# Flightcontroller.net
KiCad netlist of a schematic drawn in EAGLE
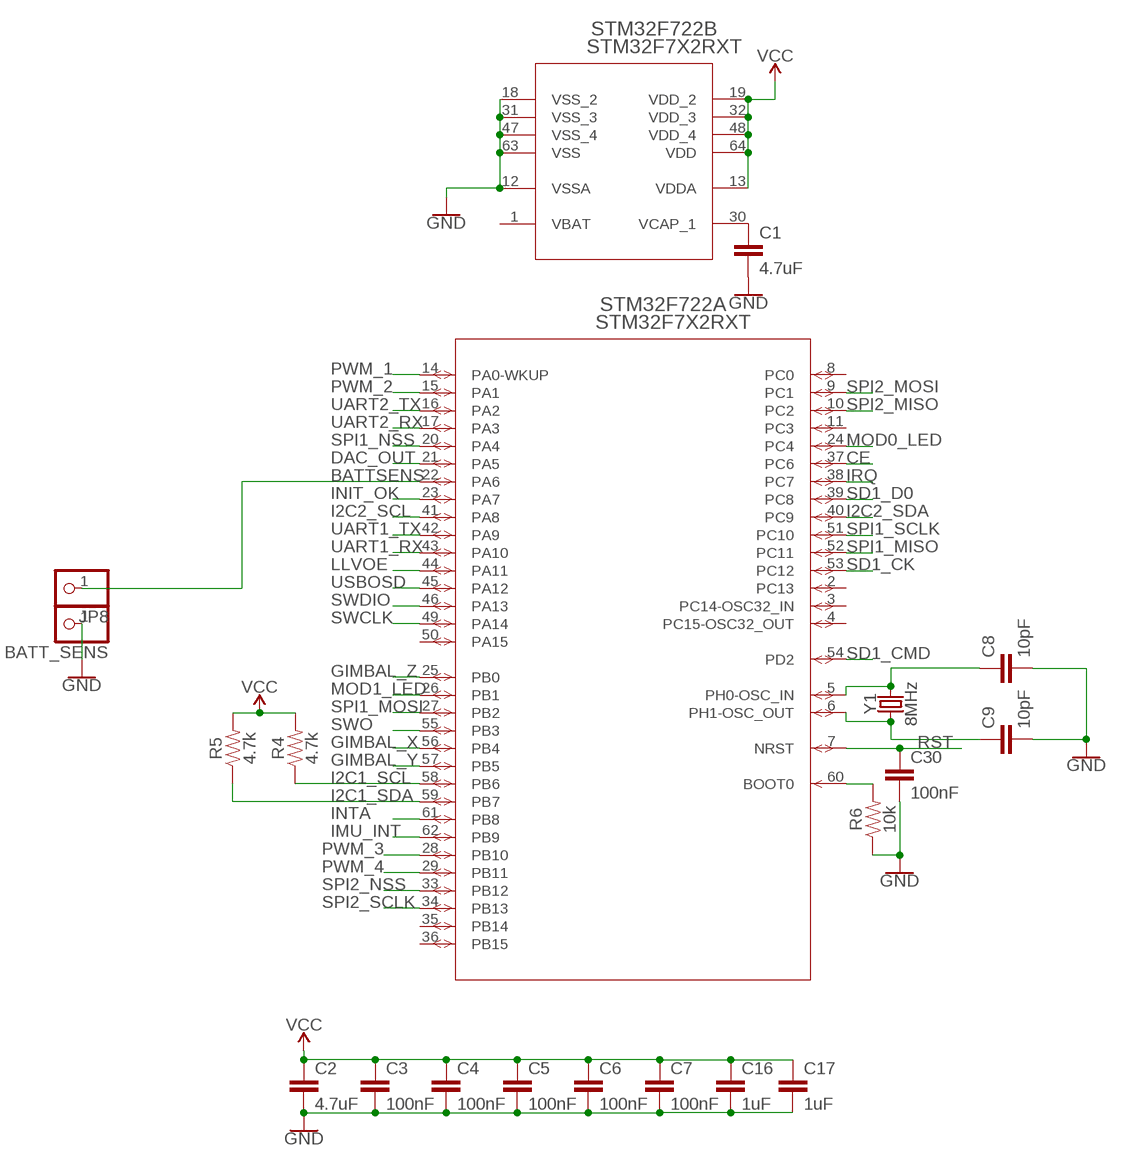
[diagram p0: schematic, sheet 1]
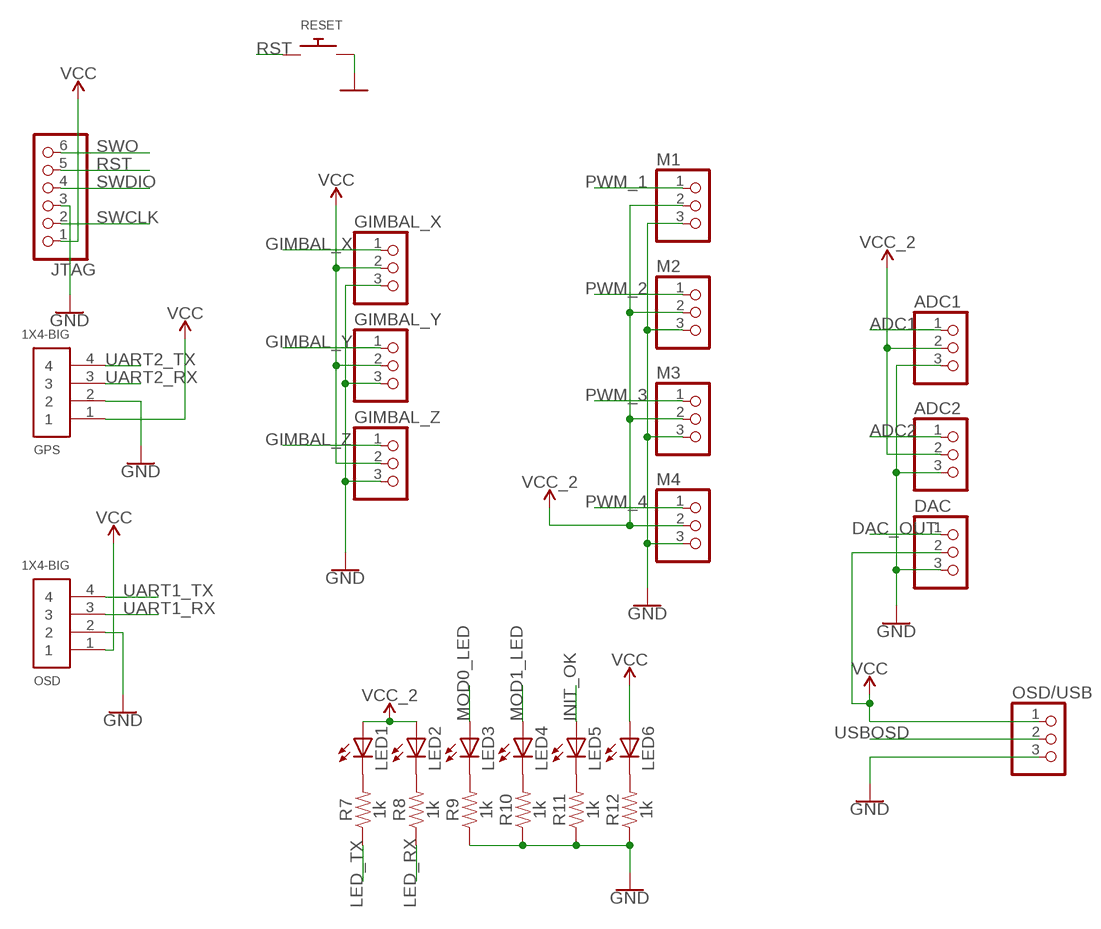
[diagram p1: schematic, sheet 2]
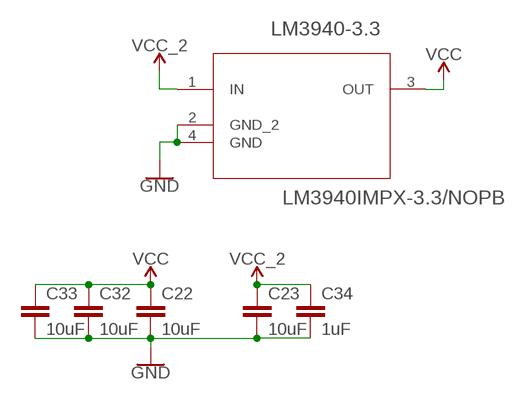
[diagram p2: schematic, sheet 3]
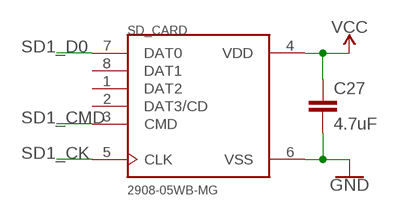
[diagram p3: schematic, sheet 4]
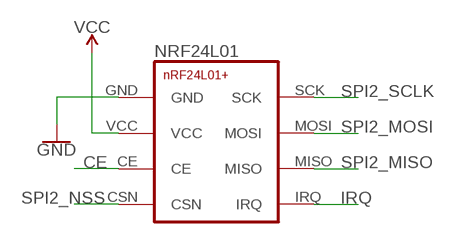
[diagram p4: schematic, sheet 5]
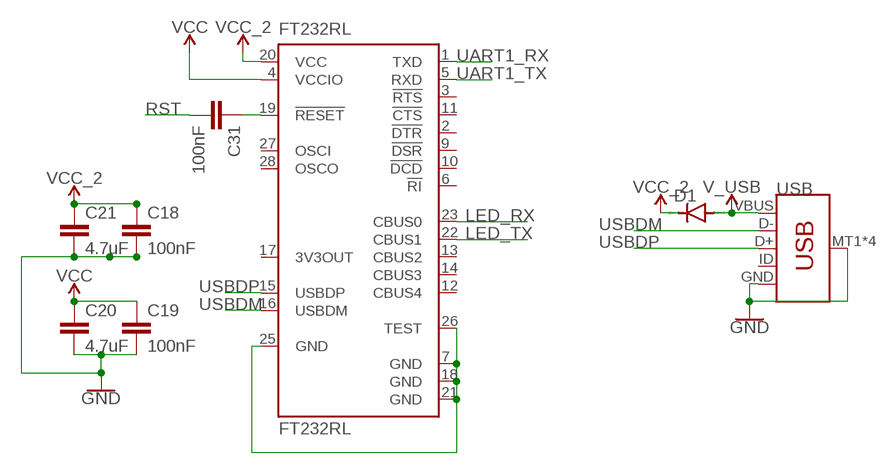
[diagram p5: schematic, sheet 6]
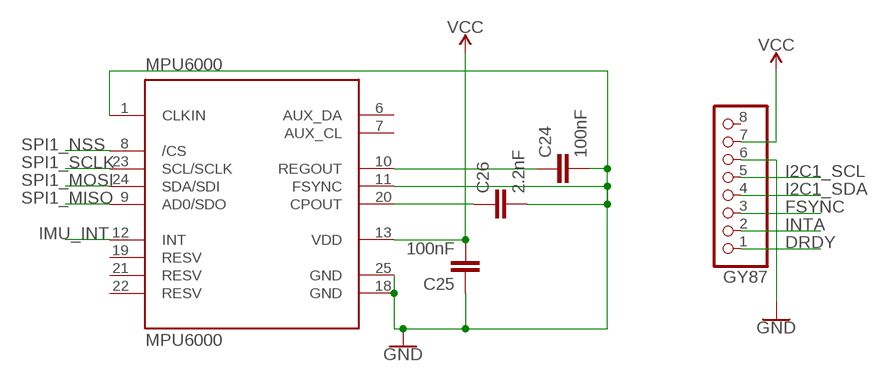
[diagram p6: schematic, sheet 7]
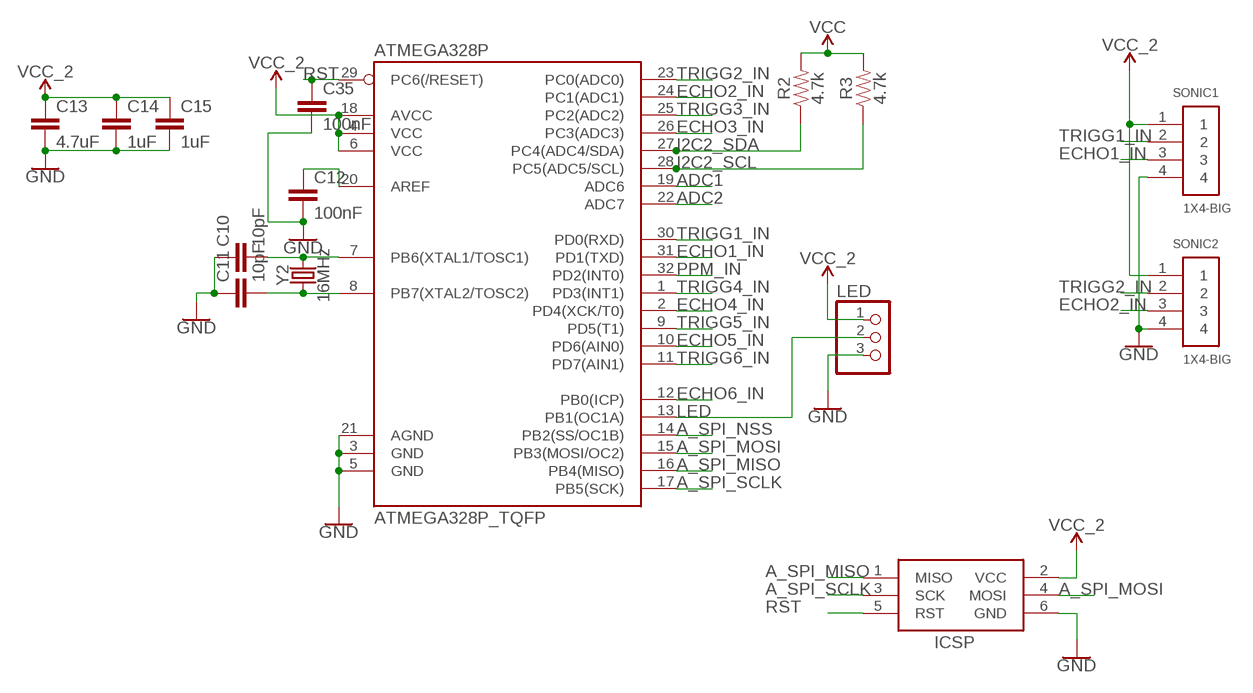
[diagram p7: schematic, sheet 8]
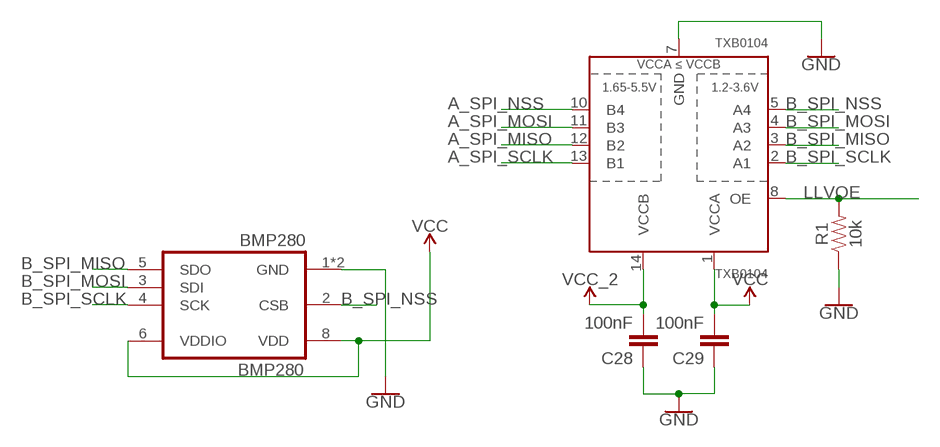
[diagram p8: schematic, sheet 9]
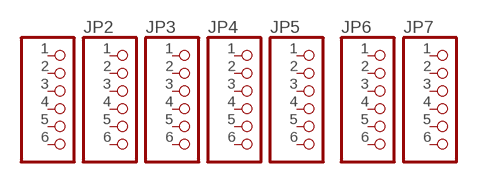
[diagram p9: schematic, sheet 10]

(export (version "E")
  (design (tool "Eeschema 10.0.6"))
  (components
    (comp (ref "C24")
      (value "100nF")
      (footprint "eagle-import:C0805")
      (libsource (lib "eagle-import") (part "C-EUC0805"))
    )
    (comp (ref "C25")
      (value "100nF")
      (footprint "eagle-import:C0805")
      (libsource (lib "eagle-import") (part "C-EUC0805"))
    )
    (comp (ref "C26")
      (value "2.2nF")
      (footprint "eagle-import:C0805")
      (libsource (lib "eagle-import") (part "C-EUC0805"))
    )
    (comp (ref "GY87")
      (value "PINHD-1X8CLEANBIG")
      (footprint "eagle-import:1X08-CLEANBIG")
      (libsource (lib "eagle-import") (part "PINHD-1X8CLEANBIG"))
    )
    (comp (ref "MPU6000")
      (value "MPU6000")
      (footprint "eagle-import:QFN50P400X400X95-25T265X275N")
      (libsource (lib "eagle-import") (part "MPU6000"))
    )
    (comp (ref "C18")
      (value "100nF")
      (footprint "eagle-import:C0805")
      (libsource (lib "eagle-import") (part "C-EUC0805"))
    )
    (comp (ref "C19")
      (value "100nF")
      (footprint "eagle-import:C0805")
      (libsource (lib "eagle-import") (part "C-EUC0805"))
    )
    (comp (ref "C20")
      (value "4.7uF")
      (footprint "eagle-import:C0805")
      (libsource (lib "eagle-import") (part "resistor_348_C-EUC0805"))
    )
    (comp (ref "C21")
      (value "4.7uF")
      (footprint "eagle-import:C0805")
      (libsource (lib "eagle-import") (part "resistor_348_C-EUC0805"))
    )
    (comp (ref "C31")
      (value "100nF")
      (footprint "eagle-import:C0805")
      (libsource (lib "eagle-import") (part "C-EUC0805"))
    )
    (comp (ref "D1")
      (value "DIODE-DO214BA")
      (footprint "eagle-import:DO214BA")
      (libsource (lib "eagle-import") (part "DIODE-DO214BA"))
    )
    (comp (ref "FT232RL")
      (value "FT232RL")
      (footprint "eagle-import:SSOP28")
      (libsource (lib "eagle-import") (part "FT232RL"))
    )
    (comp (ref "USB")
      (value "USB_MICRO-B_SMT")
      (footprint "eagle-import:USB-MICROB")
      (libsource (lib "eagle-import") (part "USB_MICRO-B_SMT"))
    )
    (comp (ref "NRF24L01")
      (value "NRF24L01+")
      (footprint "eagle-import:NRF24L01+")
      (libsource (lib "eagle-import") (part "NRF24L01+"))
    )
    (comp (ref "C22")
      (value "10uF")
      (footprint "eagle-import:C0805")
      (libsource (lib "eagle-import") (part "C-EUC0805"))
    )
    (comp (ref "C23")
      (value "10uF")
      (footprint "eagle-import:C0805")
      (libsource (lib "eagle-import") (part "C-EUC0805"))
    )
    (comp (ref "C32")
      (value "10uF")
      (footprint "eagle-import:C0805")
      (libsource (lib "eagle-import") (part "C-EUC0805"))
    )
    (comp (ref "C33")
      (value "10uF")
      (footprint "eagle-import:C0805")
      (libsource (lib "eagle-import") (part "C-EUC0805"))
    )
    (comp (ref "C34")
      (value "1uF")
      (footprint "eagle-import:C0805")
      (libsource (lib "eagle-import") (part "C-EUC0805"))
    )
    (comp (ref "LM3940-3.3")
      (value "LM3940IMPX-3.3/NOPB")
      (footprint "eagle-import:SOT230P696X180-4N")
      (fields (field (name "MF") "Texas Instruments"))
      (libsource (lib "eagle-import") (part "LM3940IMPX-3.3/NOPB"))
    )
    (comp (ref "C27")
      (value "4.7uF")
      (footprint "eagle-import:C0805")
      (libsource (lib "eagle-import") (part "resistor_348_C-EUC0805"))
    )
    (comp (ref "SD_CARD")
      (value "2908-05WB-MG")
      (footprint "eagle-import:3M_2908-05WB-MG")
      (fields (field (name "MF") "3M"))
      (libsource (lib "eagle-import") (part "2908-05WB-MG"))
    )
    (comp (ref "BMP280")
      (value "BMP280")
      (footprint "eagle-import:BMP280")
      (libsource (lib "eagle-import") (part "BMP280"))
    )
    (comp (ref "C28")
      (value "100nF")
      (footprint "eagle-import:C0805")
      (libsource (lib "eagle-import") (part "C-EUC0805"))
    )
    (comp (ref "C29")
      (value "100nF")
      (footprint "eagle-import:C0805")
      (libsource (lib "eagle-import") (part "C-EUC0805"))
    )
    (comp (ref "R1")
      (value "10k")
      (footprint "eagle-import:0603")
      (libsource (lib "eagle-import") (part "10KOHM-0603-1/10W-1%"))
    )
    (comp (ref "TXB0104")
      (value "TXB0104")
      (footprint "eagle-import:SO14")
      (libsource (lib "eagle-import") (part "TXB0104PWRSOIC14"))
    )
    (comp (ref "ADC1")
      (value "PINHD-1X3")
      (footprint "eagle-import:1X03")
      (libsource (lib "eagle-import") (part "PINHD-1X3"))
    )
    (comp (ref "ADC2")
      (value "PINHD-1X3")
      (footprint "eagle-import:1X03")
      (libsource (lib "eagle-import") (part "PINHD-1X3"))
    )
    (comp (ref "DAC")
      (value "PINHD-1X3")
      (footprint "eagle-import:1X03")
      (libsource (lib "eagle-import") (part "PINHD-1X3"))
    )
    (comp (ref "GIMBAL_X")
      (value "PINHD-1X3")
      (footprint "eagle-import:1X03")
      (libsource (lib "eagle-import") (part "PINHD-1X3"))
    )
    (comp (ref "GIMBAL_Y")
      (value "PINHD-1X3")
      (footprint "eagle-import:1X03")
      (libsource (lib "eagle-import") (part "PINHD-1X3"))
    )
    (comp (ref "GIMBAL_Z")
      (value "PINHD-1X3")
      (footprint "eagle-import:1X03")
      (libsource (lib "eagle-import") (part "PINHD-1X3"))
    )
    (comp (ref "GPS")
      (value "1X4-BIG")
      (footprint "eagle-import:1X04-BIG")
      (libsource (lib "eagle-import") (part "1X4-BIG"))
    )
    (comp (ref "JTAG")
      (value "PINHD-1X6")
      (footprint "eagle-import:1X06")
      (libsource (lib "eagle-import") (part "PINHD-1X6"))
    )
    (comp (ref "LED1")
      (value "LEDSMT1206")
      (footprint "eagle-import:1206")
      (libsource (lib "eagle-import") (part "LEDSMT1206"))
    )
    (comp (ref "LED2")
      (value "LEDSMT1206")
      (footprint "eagle-import:1206")
      (libsource (lib "eagle-import") (part "LEDSMT1206"))
    )
    (comp (ref "LED3")
      (value "LEDSMT1206")
      (footprint "eagle-import:1206")
      (libsource (lib "eagle-import") (part "LEDSMT1206"))
    )
    (comp (ref "LED4")
      (value "LEDSMT1206")
      (footprint "eagle-import:1206")
      (libsource (lib "eagle-import") (part "LEDSMT1206"))
    )
    (comp (ref "LED5")
      (value "LEDSMT1206")
      (footprint "eagle-import:1206")
      (libsource (lib "eagle-import") (part "LEDSMT1206"))
    )
    (comp (ref "LED6")
      (value "LEDSMT1206")
      (footprint "eagle-import:1206")
      (libsource (lib "eagle-import") (part "LEDSMT1206"))
    )
    (comp (ref "M1")
      (value "PINHD-1X3")
      (footprint "eagle-import:1X03")
      (libsource (lib "eagle-import") (part "PINHD-1X3"))
    )
    (comp (ref "M2")
      (value "PINHD-1X3")
      (footprint "eagle-import:1X03")
      (libsource (lib "eagle-import") (part "PINHD-1X3"))
    )
    (comp (ref "M3")
      (value "PINHD-1X3")
      (footprint "eagle-import:1X03")
      (libsource (lib "eagle-import") (part "PINHD-1X3"))
    )
    (comp (ref "M4")
      (value "PINHD-1X3")
      (footprint "eagle-import:1X03")
      (libsource (lib "eagle-import") (part "PINHD-1X3"))
    )
    (comp (ref "OSD")
      (value "1X4-BIG")
      (footprint "eagle-import:1X04-BIG")
      (libsource (lib "eagle-import") (part "1X4-BIG"))
    )
    (comp (ref "OSD/USB")
      (value "PINHD-1X3")
      (footprint "eagle-import:1X03")
      (libsource (lib "eagle-import") (part "PINHD-1X3"))
    )
    (comp (ref "R7")
      (value "1k")
      (footprint "eagle-import:0603")
      (libsource (lib "eagle-import") (part "10KOHM-0603-1/10W-1%"))
    )
    (comp (ref "R8")
      (value "1k")
      (footprint "eagle-import:0603")
      (libsource (lib "eagle-import") (part "10KOHM-0603-1/10W-1%"))
    )
    (comp (ref "R9")
      (value "1k")
      (footprint "eagle-import:0603")
      (libsource (lib "eagle-import") (part "10KOHM-0603-1/10W-1%"))
    )
    (comp (ref "R10")
      (value "1k")
      (footprint "eagle-import:0603")
      (libsource (lib "eagle-import") (part "10KOHM-0603-1/10W-1%"))
    )
    (comp (ref "R11")
      (value "1k")
      (footprint "eagle-import:0603")
      (libsource (lib "eagle-import") (part "10KOHM-0603-1/10W-1%"))
    )
    (comp (ref "R12")
      (value "1k")
      (footprint "eagle-import:0603")
      (libsource (lib "eagle-import") (part "10KOHM-0603-1/10W-1%"))
    )
    (comp (ref "RESET")
      (value "SWITCH_PUSHBUTTONC&K_KSS")
      (footprint "eagle-import:BTN_CK_KSS")
      (libsource (lib "eagle-import") (part "SWITCH_PUSHBUTTONC&K_KSS"))
    )
    (comp (ref "BATT_SENS")
      (value "PINHD-1X1")
      (footprint "eagle-import:1X01")
      (libsource (lib "eagle-import") (part "PINHD-1X1"))
    )
    (comp (ref "C1")
      (value "4.7uF")
      (footprint "eagle-import:C0805")
      (libsource (lib "eagle-import") (part "resistor_348_C-EUC0805"))
    )
    (comp (ref "C2")
      (value "4.7uF")
      (footprint "eagle-import:C0805")
      (libsource (lib "eagle-import") (part "resistor_348_C-EUC0805"))
    )
    (comp (ref "C3")
      (value "100nF")
      (footprint "eagle-import:C0805")
      (libsource (lib "eagle-import") (part "C-EUC0805"))
    )
    (comp (ref "C4")
      (value "100nF")
      (footprint "eagle-import:C0805")
      (libsource (lib "eagle-import") (part "C-EUC0805"))
    )
    (comp (ref "C5")
      (value "100nF")
      (footprint "eagle-import:C0805")
      (libsource (lib "eagle-import") (part "C-EUC0805"))
    )
    (comp (ref "C6")
      (value "100nF")
      (footprint "eagle-import:C0805")
      (libsource (lib "eagle-import") (part "C-EUC0805"))
    )
    (comp (ref "C7")
      (value "100nF")
      (footprint "eagle-import:C0805")
      (libsource (lib "eagle-import") (part "C-EUC0805"))
    )
    (comp (ref "C8")
      (value "10pF")
      (footprint "eagle-import:C0805")
      (libsource (lib "eagle-import") (part "C-EUC0805"))
    )
    (comp (ref "C9")
      (value "10pF")
      (footprint "eagle-import:C0805")
      (libsource (lib "eagle-import") (part "C-EUC0805"))
    )
    (comp (ref "C16")
      (value "1uF")
      (footprint "eagle-import:C0805")
      (libsource (lib "eagle-import") (part "C-EUC0805"))
    )
    (comp (ref "C17")
      (value "1uF")
      (footprint "eagle-import:C0805")
      (libsource (lib "eagle-import") (part "C-EUC0805"))
    )
    (comp (ref "C30")
      (value "100nF")
      (footprint "eagle-import:C0805")
      (libsource (lib "eagle-import") (part "C-EUC0805"))
    )
    (comp (ref "JP8")
      (value "PINHD-1X1")
      (footprint "eagle-import:1X01")
      (libsource (lib "eagle-import") (part "PINHD-1X1"))
    )
    (comp (ref "R4")
      (value "4.7k")
      (footprint "eagle-import:0603")
      (libsource (lib "eagle-import") (part "4.7KOHM-0603-1/10W-1%"))
    )
    (comp (ref "R5")
      (value "4.7k")
      (footprint "eagle-import:0603")
      (libsource (lib "eagle-import") (part "4.7KOHM-0603-1/10W-1%"))
    )
    (comp (ref "R6")
      (value "10k")
      (footprint "eagle-import:0603")
      (libsource (lib "eagle-import") (part "10KOHM-0603-1/10W-1%"))
    )
    (comp (ref "STM32F722")
      (value "STM32F7X2RXT")
      (footprint "eagle-import:LQFP64-10X10MM")
      (libsource (lib "eagle-import") (part "STM32F7X2RXT"))
    )
    (comp (ref "Y1")
      (value "8MHz")
      (footprint "eagle-import:CRYSTAL-SMD-5X3.2-4PAD")
      (libsource (lib "eagle-import") (part "CRYSTAL-8MHZSMD-5X3.2"))
    )
    (comp (ref "ATMEGA328P")
      (value "ATMEGA328P_TQFP")
      (footprint "eagle-import:TQFP32-08")
      (libsource (lib "eagle-import") (part "ATMEGA328P_TQFP"))
    )
    (comp (ref "C10")
      (value "10pF")
      (footprint "eagle-import:C0805")
      (libsource (lib "eagle-import") (part "C-EUC0805"))
    )
    (comp (ref "C11")
      (value "10pF")
      (footprint "eagle-import:C0805")
      (libsource (lib "eagle-import") (part "C-EUC0805"))
    )
    (comp (ref "C12")
      (value "100nF")
      (footprint "eagle-import:C0805")
      (libsource (lib "eagle-import") (part "C-EUC0805"))
    )
    (comp (ref "C13")
      (value "4.7uF")
      (footprint "eagle-import:C0805")
      (libsource (lib "eagle-import") (part "resistor_348_C-EUC0805"))
    )
    (comp (ref "C14")
      (value "1uF")
      (footprint "eagle-import:C0805")
      (libsource (lib "eagle-import") (part "C-EUC0805"))
    )
    (comp (ref "C15")
      (value "1uF")
      (footprint "eagle-import:C0805")
      (libsource (lib "eagle-import") (part "C-EUC0805"))
    )
    (comp (ref "C35")
      (value "100nF")
      (footprint "eagle-import:C0805")
      (libsource (lib "eagle-import") (part "C-EUC0805"))
    )
    (comp (ref "ICSP")
      (value "AVRISP-6")
      (footprint "eagle-import:AVRISP")
      (libsource (lib "eagle-import") (part "AVRISP-6"))
    )
    (comp (ref "LED")
      (value "PINHD-1X3")
      (footprint "eagle-import:1X03")
      (libsource (lib "eagle-import") (part "PINHD-1X3"))
    )
    (comp (ref "R2")
      (value "4.7k")
      (footprint "eagle-import:0603")
      (libsource (lib "eagle-import") (part "4.7KOHM-0603-1/10W-1%"))
    )
    (comp (ref "R3")
      (value "4.7k")
      (footprint "eagle-import:0603")
      (libsource (lib "eagle-import") (part "4.7KOHM-0603-1/10W-1%"))
    )
    (comp (ref "SONIC1")
      (value "1X4-BIG")
      (footprint "eagle-import:1X04-BIG")
      (libsource (lib "eagle-import") (part "1X4-BIG"))
    )
    (comp (ref "SONIC2")
      (value "1X4-BIG")
      (footprint "eagle-import:1X04-BIG")
      (libsource (lib "eagle-import") (part "1X4-BIG"))
    )
    (comp (ref "Y2")
      (value "16MHz")
      (footprint "eagle-import:CRYSTAL-SMD-5X3.2-4PAD")
      (libsource (lib "eagle-import") (part "CRYSTAL-16MHZSMD-5X3.2"))
    )
    (comp (ref "JP1")
      (value "PINHD-1X6")
      (footprint "eagle-import:1X06")
      (libsource (lib "eagle-import") (part "PINHD-1X6"))
    )
    (comp (ref "JP2")
      (value "PINHD-1X6")
      (footprint "eagle-import:1X06")
      (libsource (lib "eagle-import") (part "PINHD-1X6"))
    )
    (comp (ref "JP3")
      (value "PINHD-1X6")
      (footprint "eagle-import:1X06")
      (libsource (lib "eagle-import") (part "PINHD-1X6"))
    )
    (comp (ref "JP4")
      (value "PINHD-1X6")
      (footprint "eagle-import:1X06")
      (libsource (lib "eagle-import") (part "PINHD-1X6"))
    )
    (comp (ref "JP5")
      (value "PINHD-1X6")
      (footprint "eagle-import:1X06")
      (libsource (lib "eagle-import") (part "PINHD-1X6"))
    )
    (comp (ref "JP6")
      (value "PINHD-1X6")
      (footprint "eagle-import:1X06")
      (libsource (lib "eagle-import") (part "PINHD-1X6"))
    )
    (comp (ref "JP7")
      (value "PINHD-1X6")
      (footprint "eagle-import:1X06")
      (libsource (lib "eagle-import") (part "PINHD-1X6"))
    )
  )
  (nets
    (net (code "1") (name "ADC1") (class "Default")
      (node (ref "ADC1") (pin "1") (pinfunction "1_1") (pintype "passive"))
      (node (ref "ATMEGA328P") (pin "19") (pinfunction "ADC6_19") (pintype "bidirectional"))
    )
    (net (code "2") (name "ADC2") (class "Default")
      (node (ref "ADC2") (pin "1") (pinfunction "1_1") (pintype "passive"))
      (node (ref "ATMEGA328P") (pin "22") (pinfunction "ADC7_22") (pintype "bidirectional"))
    )
    (net (code "3") (name "A_SPI_MISO") (class "Default")
      (node (ref "ATMEGA328P") (pin "16") (pinfunction "PB4(MISO)_16") (pintype "bidirectional"))
      (node (ref "ICSP") (pin "1") (pinfunction "MISO_1") (pintype "input"))
      (node (ref "TXB0104") (pin "12") (pinfunction "B2_12") (pintype "bidirectional"))
    )
    (net (code "4") (name "A_SPI_MOSI") (class "Default")
      (node (ref "ATMEGA328P") (pin "15") (pinfunction "PB3(MOSI/OC2)_15") (pintype "bidirectional"))
      (node (ref "ICSP") (pin "4") (pinfunction "MOSI_4") (pintype "output"))
      (node (ref "TXB0104") (pin "11") (pinfunction "B3_11") (pintype "bidirectional"))
    )
    (net (code "5") (name "A_SPI_NSS") (class "Default")
      (node (ref "ATMEGA328P") (pin "14") (pinfunction "PB2(SS/OC1B)_14") (pintype "bidirectional"))
      (node (ref "TXB0104") (pin "10") (pinfunction "B4_10") (pintype "bidirectional"))
    )
    (net (code "6") (name "A_SPI_SCLK") (class "Default")
      (node (ref "ATMEGA328P") (pin "17") (pinfunction "PB5(SCK)_17") (pintype "bidirectional"))
      (node (ref "ICSP") (pin "3") (pinfunction "SCK_3") (pintype "output"))
      (node (ref "TXB0104") (pin "13") (pinfunction "B1_13") (pintype "bidirectional"))
    )
    (net (code "7") (name "BATTSENS") (class "Default")
      (node (ref "JP8") (pin "1") (pinfunction "1_1") (pintype "passive"))
      (node (ref "STM32F722") (pin "22") (pinfunction "PA6_22") (pintype "bidirectional"))
    )
    (net (code "8") (name "B_SPI_MISO") (class "Default")
      (node (ref "BMP280") (pin "5") (pinfunction "SDO_5") (pintype "input"))
      (node (ref "TXB0104") (pin "3") (pinfunction "A2_3") (pintype "bidirectional"))
    )
    (net (code "9") (name "B_SPI_MOSI") (class "Default")
      (node (ref "BMP280") (pin "3") (pinfunction "SDI_3") (pintype "bidirectional"))
      (node (ref "TXB0104") (pin "4") (pinfunction "A3_4") (pintype "bidirectional"))
    )
    (net (code "10") (name "B_SPI_NSS") (class "Default")
      (node (ref "BMP280") (pin "2") (pinfunction "CSB_2") (pintype "input"))
      (node (ref "TXB0104") (pin "5") (pinfunction "A4_5") (pintype "bidirectional"))
    )
    (net (code "11") (name "B_SPI_SCLK") (class "Default")
      (node (ref "BMP280") (pin "4") (pinfunction "SCK_4") (pintype "bidirectional"))
      (node (ref "TXB0104") (pin "2") (pinfunction "A1_2") (pintype "bidirectional"))
    )
    (net (code "12") (name "CE") (class "Default")
      (node (ref "NRF24L01") (pin "CE") (pinfunction "CE_CE") (pintype "bidirectional"))
      (node (ref "STM32F722") (pin "37") (pinfunction "PC6_37") (pintype "bidirectional"))
    )
    (net (code "13") (name "DAC_OUT") (class "Default")
      (node (ref "DAC") (pin "1") (pinfunction "1_1") (pintype "passive"))
      (node (ref "STM32F722") (pin "21") (pinfunction "PA5_21") (pintype "bidirectional"))
    )
    (net (code "14") (name "DRDY") (class "Default")
      (node (ref "GY87") (pin "1") (pinfunction "1_1") (pintype "passive"))
    )
    (net (code "15") (name "ECHO1_IN") (class "Default")
      (node (ref "ATMEGA328P") (pin "31") (pinfunction "PD1(TXD)_31") (pintype "bidirectional"))
      (node (ref "SONIC1") (pin "3") (pinfunction "3_3") (pintype "bidirectional"))
    )
    (net (code "16") (name "ECHO2_IN") (class "Default")
      (node (ref "ATMEGA328P") (pin "24") (pinfunction "PC1(ADC1)_24") (pintype "bidirectional"))
      (node (ref "SONIC2") (pin "3") (pinfunction "3_3") (pintype "bidirectional"))
    )
    (net (code "17") (name "ECHO3_IN") (class "Default")
      (node (ref "ATMEGA328P") (pin "26") (pinfunction "PC3(ADC3)_26") (pintype "bidirectional"))
    )
    (net (code "18") (name "ECHO4_IN") (class "Default")
      (node (ref "ATMEGA328P") (pin "2") (pinfunction "PD4(XCK/T0)_2") (pintype "bidirectional"))
    )
    (net (code "19") (name "ECHO5_IN") (class "Default")
      (node (ref "ATMEGA328P") (pin "10") (pinfunction "PD6(AIN0)_10") (pintype "bidirectional"))
    )
    (net (code "20") (name "ECHO6_IN") (class "Default")
      (node (ref "ATMEGA328P") (pin "12") (pinfunction "PB0(ICP)_12") (pintype "bidirectional"))
    )
    (net (code "21") (name "FSYNC") (class "Default")
      (node (ref "GY87") (pin "3") (pinfunction "3_3") (pintype "passive"))
    )
    (net (code "22") (name "GIMBAL_X") (class "Default")
      (node (ref "GIMBAL_X") (pin "1") (pinfunction "1_1") (pintype "passive"))
      (node (ref "STM32F722") (pin "56") (pinfunction "PB4_56") (pintype "bidirectional"))
    )
    (net (code "23") (name "GIMBAL_Y") (class "Default")
      (node (ref "GIMBAL_Y") (pin "1") (pinfunction "1_1") (pintype "passive"))
      (node (ref "STM32F722") (pin "57") (pinfunction "PB5_57") (pintype "bidirectional"))
    )
    (net (code "24") (name "GIMBAL_Z") (class "Default")
      (node (ref "GIMBAL_Z") (pin "1") (pinfunction "1_1") (pintype "passive"))
      (node (ref "STM32F722") (pin "25") (pinfunction "PB0_25") (pintype "bidirectional"))
    )
    (net (code "25") (name "GND") (class "Default")
      (node (ref "ADC1") (pin "3") (pinfunction "3_3") (pintype "passive"))
      (node (ref "ADC2") (pin "3") (pinfunction "3_3") (pintype "passive"))
      (node (ref "ATMEGA328P") (pin "21") (pinfunction "AGND_21") (pintype "bidirectional"))
      (node (ref "ATMEGA328P") (pin "3") (pinfunction "GND_3") (pintype "bidirectional"))
      (node (ref "ATMEGA328P") (pin "5") (pinfunction "GND_5") (pintype "bidirectional"))
      (node (ref "BATT_SENS") (pin "1") (pinfunction "1_1") (pintype "passive"))
      (node (ref "BMP280") (pin "1") (pinfunction "GND_1") (pintype "power_in"))
      (node (ref "BMP280") (pin "7") (pinfunction "GND_7") (pintype "power_in"))
      (node (ref "C1") (pin "2") (pinfunction "2_2") (pintype "passive"))
      (node (ref "C10") (pin "1") (pinfunction "1_1") (pintype "passive"))
      (node (ref "C11") (pin "1") (pinfunction "1_1") (pintype "passive"))
      (node (ref "C12") (pin "2") (pinfunction "2_2") (pintype "passive"))
      (node (ref "C13") (pin "2") (pinfunction "2_2") (pintype "passive"))
      (node (ref "C14") (pin "2") (pinfunction "2_2") (pintype "passive"))
      (node (ref "C15") (pin "2") (pinfunction "2_2") (pintype "passive"))
      (node (ref "C16") (pin "2") (pinfunction "2_2") (pintype "passive"))
      (node (ref "C17") (pin "2") (pinfunction "2_2") (pintype "passive"))
      (node (ref "C18") (pin "2") (pinfunction "2_2") (pintype "passive"))
      (node (ref "C19") (pin "2") (pinfunction "2_2") (pintype "passive"))
      (node (ref "C2") (pin "2") (pinfunction "2_2") (pintype "passive"))
      (node (ref "C20") (pin "2") (pinfunction "2_2") (pintype "passive"))
      (node (ref "C21") (pin "2") (pinfunction "2_2") (pintype "passive"))
      (node (ref "C22") (pin "2") (pinfunction "2_2") (pintype "passive"))
      (node (ref "C23") (pin "2") (pinfunction "2_2") (pintype "passive"))
      (node (ref "C24") (pin "2") (pinfunction "2_2") (pintype "passive"))
      (node (ref "C25") (pin "1") (pinfunction "1_1") (pintype "passive"))
      (node (ref "C26") (pin "2") (pinfunction "2_2") (pintype "passive"))
      (node (ref "C27") (pin "2") (pinfunction "2_2") (pintype "passive"))
      (node (ref "C28") (pin "1") (pinfunction "1_1") (pintype "passive"))
      (node (ref "C29") (pin "1") (pinfunction "1_1") (pintype "passive"))
      (node (ref "C3") (pin "2") (pinfunction "2_2") (pintype "passive"))
      (node (ref "C30") (pin "2") (pinfunction "2_2") (pintype "passive"))
      (node (ref "C32") (pin "2") (pinfunction "2_2") (pintype "passive"))
      (node (ref "C33") (pin "2") (pinfunction "2_2") (pintype "passive"))
      (node (ref "C34") (pin "2") (pinfunction "2_2") (pintype "passive"))
      (node (ref "C35") (pin "2") (pinfunction "2_2") (pintype "passive"))
      (node (ref "C4") (pin "2") (pinfunction "2_2") (pintype "passive"))
      (node (ref "C5") (pin "2") (pinfunction "2_2") (pintype "passive"))
      (node (ref "C6") (pin "2") (pinfunction "2_2") (pintype "passive"))
      (node (ref "C7") (pin "2") (pinfunction "2_2") (pintype "passive"))
      (node (ref "C8") (pin "2") (pinfunction "2_2") (pintype "passive"))
      (node (ref "C9") (pin "2") (pinfunction "2_2") (pintype "passive"))
      (node (ref "DAC") (pin "3") (pinfunction "3_3") (pintype "passive"))
      (node (ref "GIMBAL_X") (pin "3") (pinfunction "3_3") (pintype "passive"))
      (node (ref "GIMBAL_Y") (pin "3") (pinfunction "3_3") (pintype "passive"))
      (node (ref "GIMBAL_Z") (pin "3") (pinfunction "3_3") (pintype "passive"))
      (node (ref "GPS") (pin "2") (pinfunction "2_2") (pintype "bidirectional"))
      (node (ref "GY87") (pin "6") (pinfunction "6_6") (pintype "passive"))
      (node (ref "ICSP") (pin "6") (pinfunction "GND_6") (pintype "power_in"))
      (node (ref "JTAG") (pin "3") (pinfunction "3_3") (pintype "passive"))
      (node (ref "LED") (pin "3") (pinfunction "3_3") (pintype "passive"))
      (node (ref "LM3940-3.3") (pin "2") (pinfunction "GND_2_2") (pintype "passive"))
      (node (ref "LM3940-3.3") (pin "4") (pinfunction "GND_4") (pintype "passive"))
      (node (ref "M1") (pin "3") (pinfunction "3_3") (pintype "passive"))
      (node (ref "M2") (pin "3") (pinfunction "3_3") (pintype "passive"))
      (node (ref "M3") (pin "3") (pinfunction "3_3") (pintype "passive"))
      (node (ref "M4") (pin "3") (pinfunction "3_3") (pintype "passive"))
      (node (ref "MPU6000") (pin "1") (pinfunction "CLKIN_1") (pintype "input"))
      (node (ref "MPU6000") (pin "11") (pinfunction "FSYNC_11") (pintype "input"))
      (node (ref "MPU6000") (pin "18") (pinfunction "GND_18") (pintype "power_in"))
      (node (ref "MPU6000") (pin "25") (pinfunction "GND_25") (pintype "power_in"))
      (node (ref "NRF24L01") (pin "GND") (pinfunction "GND_GND") (pintype "power_in"))
      (node (ref "OSD") (pin "2") (pinfunction "2_2") (pintype "bidirectional"))
      (node (ref "OSD/USB") (pin "3") (pinfunction "3_3") (pintype "passive"))
      (node (ref "R1") (pin "1") (pinfunction "1_1") (pintype "passive"))
      (node (ref "R10") (pin "1") (pinfunction "1_1") (pintype "passive"))
      (node (ref "R11") (pin "1") (pinfunction "1_1") (pintype "passive"))
      (node (ref "R12") (pin "1") (pinfunction "1_1") (pintype "passive"))
      (node (ref "R6") (pin "1") (pinfunction "1_1") (pintype "passive"))
      (node (ref "R9") (pin "1") (pinfunction "1_1") (pintype "passive"))
      (node (ref "RESET") (pin "P$2") (pinfunction "P$2_P$2") (pintype "passive"))
      (node (ref "SD_CARD") (pin "6") (pinfunction "VSS_6") (pintype "power_in"))
      (node (ref "SONIC1") (pin "4") (pinfunction "4_4") (pintype "bidirectional"))
      (node (ref "SONIC2") (pin "4") (pinfunction "4_4") (pintype "bidirectional"))
      (node (ref "STM32F722") (pin "12") (pinfunction "VSSA_12") (pintype "power_in"))
      (node (ref "STM32F722") (pin "18") (pinfunction "VSS_2_18") (pintype "power_in"))
      (node (ref "STM32F722") (pin "31") (pinfunction "VSS_3_31") (pintype "power_in"))
      (node (ref "STM32F722") (pin "47") (pinfunction "VSS_4_47") (pintype "power_in"))
      (node (ref "STM32F722") (pin "63") (pinfunction "VSS_63") (pintype "power_in"))
      (node (ref "TXB0104") (pin "7") (pinfunction "GND_7") (pintype "bidirectional"))
      (node (ref "USB") (pin "GND") (pinfunction "GND_GND") (pintype "power_in"))
      (node (ref "USB") (pin "MT1") (pinfunction "SHIELD_MT1") (pintype "bidirectional"))
      (node (ref "USB") (pin "MT2") (pinfunction "SHIELD_MT2") (pintype "bidirectional"))
      (node (ref "USB") (pin "P$1") (pinfunction "SHIELD_P$1") (pintype "bidirectional"))
      (node (ref "USB") (pin "P$2") (pinfunction "SHIELD_P$2") (pintype "bidirectional"))
    )
    (net (code "26") (name "I2C1_SCL") (class "Default")
      (node (ref "GY87") (pin "5") (pinfunction "5_5") (pintype "passive"))
      (node (ref "R4") (pin "1") (pinfunction "1_1") (pintype "passive"))
      (node (ref "STM32F722") (pin "58") (pinfunction "PB6_58") (pintype "bidirectional"))
    )
    (net (code "27") (name "I2C1_SDA") (class "Default")
      (node (ref "GY87") (pin "4") (pinfunction "4_4") (pintype "passive"))
      (node (ref "R5") (pin "1") (pinfunction "1_1") (pintype "passive"))
      (node (ref "STM32F722") (pin "59") (pinfunction "PB7_59") (pintype "bidirectional"))
    )
    (net (code "28") (name "I2C2_SCL") (class "Default")
      (node (ref "ATMEGA328P") (pin "28") (pinfunction "PC5(ADC5/SCL)_28") (pintype "bidirectional"))
      (node (ref "R3") (pin "1") (pinfunction "1_1") (pintype "passive"))
      (node (ref "STM32F722") (pin "41") (pinfunction "PA8_41") (pintype "bidirectional"))
    )
    (net (code "29") (name "I2C2_SDA") (class "Default")
      (node (ref "ATMEGA328P") (pin "27") (pinfunction "PC4(ADC4/SDA)_27") (pintype "bidirectional"))
      (node (ref "R2") (pin "1") (pinfunction "1_1") (pintype "passive"))
      (node (ref "STM32F722") (pin "40") (pinfunction "PC9_40") (pintype "bidirectional"))
    )
    (net (code "30") (name "IMU_INT") (class "Default")
      (node (ref "MPU6000") (pin "12") (pinfunction "INT_12") (pintype "open_collector"))
      (node (ref "STM32F722") (pin "62") (pinfunction "PB9_62") (pintype "bidirectional"))
    )
    (net (code "31") (name "INIT_OK") (class "Default")
      (node (ref "LED5") (pin "A") (pinfunction "A_A") (pintype "passive"))
      (node (ref "STM32F722") (pin "23") (pinfunction "PA7_23") (pintype "bidirectional"))
    )
    (net (code "32") (name "INTA") (class "Default")
      (node (ref "GY87") (pin "2") (pinfunction "2_2") (pintype "passive"))
      (node (ref "STM32F722") (pin "61") (pinfunction "PB8_61") (pintype "bidirectional"))
    )
    (net (code "33") (name "IRQ") (class "Default")
      (node (ref "NRF24L01") (pin "IRQ") (pinfunction "IRQ_IRQ") (pintype "bidirectional"))
      (node (ref "STM32F722") (pin "38") (pinfunction "PC7_38") (pintype "bidirectional"))
    )
    (net (code "34") (name "LED") (class "Default")
      (node (ref "ATMEGA328P") (pin "13") (pinfunction "PB1(OC1A)_13") (pintype "bidirectional"))
      (node (ref "LED") (pin "2") (pinfunction "2_2") (pintype "passive"))
    )
    (net (code "35") (name "LED_RX") (class "Default")
      (node (ref "FT232RL") (pin "23") (pinfunction "CBUS0_23") (pintype "bidirectional"))
      (node (ref "R8") (pin "1") (pinfunction "1_1") (pintype "passive"))
    )
    (net (code "36") (name "LED_TX") (class "Default")
      (node (ref "FT232RL") (pin "22") (pinfunction "CBUS1_22") (pintype "bidirectional"))
      (node (ref "R7") (pin "1") (pinfunction "1_1") (pintype "passive"))
    )
    (net (code "37") (name "LLVOE") (class "Default")
      (node (ref "R1") (pin "2") (pinfunction "2_2") (pintype "passive"))
      (node (ref "STM32F722") (pin "44") (pinfunction "PA11_44") (pintype "bidirectional"))
      (node (ref "TXB0104") (pin "8") (pinfunction "OE_8") (pintype "bidirectional"))
    )
    (net (code "38") (name "MOD0_LED") (class "Default")
      (node (ref "LED3") (pin "A") (pinfunction "A_A") (pintype "passive"))
      (node (ref "STM32F722") (pin "24") (pinfunction "PC4_24") (pintype "bidirectional"))
    )
    (net (code "39") (name "MOD1_LED") (class "Default")
      (node (ref "LED4") (pin "A") (pinfunction "A_A") (pintype "passive"))
      (node (ref "STM32F722") (pin "26") (pinfunction "PB1_26") (pintype "bidirectional"))
    )
    (net (code "40") (name "Net-(ATMEGA328P-AREF)") (class "Default")
      (node (ref "ATMEGA328P") (pin "20") (pinfunction "AREF_20") (pintype "bidirectional"))
      (node (ref "C12") (pin "1") (pinfunction "1_1") (pintype "passive"))
    )
    (net (code "41") (name "Net-(ATMEGA328P-PB6(XTAL1{slash}TOSC1))") (class "Default")
      (node (ref "ATMEGA328P") (pin "7") (pinfunction "PB6(XTAL1/TOSC1)_7") (pintype "bidirectional"))
      (node (ref "C10") (pin "2") (pinfunction "2_2") (pintype "passive"))
      (node (ref "Y2") (pin "3") (pinfunction "2_3") (pintype "passive"))
    )
    (net (code "42") (name "Net-(ATMEGA328P-PB7(XTAL2{slash}TOSC2))") (class "Default")
      (node (ref "ATMEGA328P") (pin "8") (pinfunction "PB7(XTAL2/TOSC2)_8") (pintype "bidirectional"))
      (node (ref "C11") (pin "2") (pinfunction "2_2") (pintype "passive"))
      (node (ref "Y2") (pin "1") (pinfunction "1_1") (pintype "passive"))
    )
    (net (code "43") (name "Net-(FT232RL-TEST)") (class "Default")
      (node (ref "FT232RL") (pin "18") (pinfunction "GND_18") (pintype "power_in"))
      (node (ref "FT232RL") (pin "21") (pinfunction "GND_21") (pintype "power_in"))
      (node (ref "FT232RL") (pin "25") (pinfunction "GND_25") (pintype "power_in"))
      (node (ref "FT232RL") (pin "26") (pinfunction "TEST_26") (pintype "input"))
      (node (ref "FT232RL") (pin "7") (pinfunction "GND_7") (pintype "power_in"))
    )
    (net (code "44") (name "Net-(FT232RL-~{RESET})") (class "Default")
      (node (ref "C31") (pin "1") (pinfunction "1_1") (pintype "passive"))
      (node (ref "FT232RL") (pin "19") (pinfunction "~{RESET}_19") (pintype "input"))
    )
    (net (code "45") (name "Net-(LED1-PadC)") (class "Default")
      (node (ref "LED1") (pin "C") (pinfunction "C_C") (pintype "passive"))
      (node (ref "R7") (pin "2") (pinfunction "2_2") (pintype "passive"))
    )
    (net (code "46") (name "Net-(LED2-PadC)") (class "Default")
      (node (ref "LED2") (pin "C") (pinfunction "C_C") (pintype "passive"))
      (node (ref "R8") (pin "2") (pinfunction "2_2") (pintype "passive"))
    )
    (net (code "47") (name "Net-(LED3-PadC)") (class "Default")
      (node (ref "LED3") (pin "C") (pinfunction "C_C") (pintype "passive"))
      (node (ref "R9") (pin "2") (pinfunction "2_2") (pintype "passive"))
    )
    (net (code "48") (name "Net-(LED4-PadC)") (class "Default")
      (node (ref "LED4") (pin "C") (pinfunction "C_C") (pintype "passive"))
      (node (ref "R10") (pin "2") (pinfunction "2_2") (pintype "passive"))
    )
    (net (code "49") (name "Net-(LED5-PadC)") (class "Default")
      (node (ref "LED5") (pin "C") (pinfunction "C_C") (pintype "passive"))
      (node (ref "R11") (pin "2") (pinfunction "2_2") (pintype "passive"))
    )
    (net (code "50") (name "Net-(LED6-PadC)") (class "Default")
      (node (ref "LED6") (pin "C") (pinfunction "C_C") (pintype "passive"))
      (node (ref "R12") (pin "2") (pinfunction "2_2") (pintype "passive"))
    )
    (net (code "51") (name "Net-(MPU6000A-CPOUT)") (class "Default")
      (node (ref "C26") (pin "1") (pinfunction "1_1") (pintype "passive"))
      (node (ref "MPU6000") (pin "20") (pinfunction "CPOUT_20") (pintype "output"))
    )
    (net (code "52") (name "Net-(MPU6000A-REGOUT)") (class "Default")
      (node (ref "C24") (pin "1") (pinfunction "1_1") (pintype "passive"))
      (node (ref "MPU6000") (pin "10") (pinfunction "REGOUT_10") (pintype "output"))
    )
    (net (code "53") (name "Net-(STM32F722A-BOOT0)") (class "Default")
      (node (ref "R6") (pin "2") (pinfunction "2_2") (pintype "passive"))
      (node (ref "STM32F722") (pin "60") (pinfunction "BOOT0_60") (pintype "input"))
    )
    (net (code "54") (name "Net-(STM32F722A-PH0-OSC_IN)") (class "Default")
      (node (ref "C8") (pin "1") (pinfunction "1_1") (pintype "passive"))
      (node (ref "STM32F722") (pin "5") (pinfunction "PH0-OSC_IN_5") (pintype "bidirectional"))
      (node (ref "Y1") (pin "3") (pinfunction "2_3") (pintype "passive"))
    )
    (net (code "55") (name "Net-(STM32F722A-PH1-OSC_OUT)") (class "Default")
      (node (ref "C9") (pin "1") (pinfunction "1_1") (pintype "passive"))
      (node (ref "STM32F722") (pin "6") (pinfunction "PH1-OSC_OUT_6") (pintype "bidirectional"))
      (node (ref "Y1") (pin "1") (pinfunction "1_1") (pintype "passive"))
    )
    (net (code "56") (name "Net-(STM32F722B-VCAP_1)") (class "Default")
      (node (ref "C1") (pin "1") (pinfunction "1_1") (pintype "passive"))
      (node (ref "STM32F722") (pin "30") (pinfunction "VCAP_1_30") (pintype "power_in"))
    )
    (net (code "57") (name "PPM_IN") (class "Default")
      (node (ref "ATMEGA328P") (pin "32") (pinfunction "PD2(INT0)_32") (pintype "bidirectional"))
    )
    (net (code "58") (name "PWM_1") (class "Default")
      (node (ref "M1") (pin "1") (pinfunction "1_1") (pintype "passive"))
      (node (ref "STM32F722") (pin "14") (pinfunction "PA0-WKUP_14") (pintype "bidirectional"))
    )
    (net (code "59") (name "PWM_2") (class "Default")
      (node (ref "M2") (pin "1") (pinfunction "1_1") (pintype "passive"))
      (node (ref "STM32F722") (pin "15") (pinfunction "PA1_15") (pintype "bidirectional"))
    )
    (net (code "60") (name "PWM_3") (class "Default")
      (node (ref "M3") (pin "1") (pinfunction "1_1") (pintype "passive"))
      (node (ref "STM32F722") (pin "28") (pinfunction "PB10_28") (pintype "bidirectional"))
    )
    (net (code "61") (name "PWM_4") (class "Default")
      (node (ref "M4") (pin "1") (pinfunction "1_1") (pintype "passive"))
      (node (ref "STM32F722") (pin "29") (pinfunction "PB11_29") (pintype "bidirectional"))
    )
    (net (code "62") (name "RST") (class "Default")
      (node (ref "ATMEGA328P") (pin "29") (pinfunction "PC6(/RESET)_29") (pintype "bidirectional"))
      (node (ref "C30") (pin "1") (pinfunction "1_1") (pintype "passive"))
      (node (ref "C31") (pin "2") (pinfunction "2_2") (pintype "passive"))
      (node (ref "C35") (pin "1") (pinfunction "1_1") (pintype "passive"))
      (node (ref "ICSP") (pin "5") (pinfunction "RST_5") (pintype "output"))
      (node (ref "JTAG") (pin "5") (pinfunction "5_5") (pintype "passive"))
      (node (ref "RESET") (pin "P$1") (pinfunction "P$1_P$1") (pintype "passive"))
      (node (ref "STM32F722") (pin "7") (pinfunction "NRST_7") (pintype "bidirectional"))
    )
    (net (code "63") (name "SD1_CK") (class "Default")
      (node (ref "SD_CARD") (pin "5") (pinfunction "CLK_5") (pintype "bidirectional"))
      (node (ref "STM32F722") (pin "53") (pinfunction "PC12_53") (pintype "bidirectional"))
    )
    (net (code "64") (name "SD1_CMD") (class "Default")
      (node (ref "SD_CARD") (pin "3") (pinfunction "CMD_3") (pintype "bidirectional"))
      (node (ref "STM32F722") (pin "54") (pinfunction "PD2_54") (pintype "bidirectional"))
    )
    (net (code "65") (name "SD1_D0") (class "Default")
      (node (ref "SD_CARD") (pin "7") (pinfunction "DAT0_7") (pintype "bidirectional"))
      (node (ref "STM32F722") (pin "39") (pinfunction "PC8_39") (pintype "bidirectional"))
    )
    (net (code "66") (name "SPI1_MISO") (class "Default")
      (node (ref "MPU6000") (pin "9") (pinfunction "AD0/SDO_9") (pintype "bidirectional"))
      (node (ref "STM32F722") (pin "52") (pinfunction "PC11_52") (pintype "bidirectional"))
    )
    (net (code "67") (name "SPI1_MOSI") (class "Default")
      (node (ref "MPU6000") (pin "24") (pinfunction "SDA/SDI_24") (pintype "bidirectional"))
      (node (ref "STM32F722") (pin "27") (pinfunction "PB2_27") (pintype "bidirectional"))
    )
    (net (code "68") (name "SPI1_NSS") (class "Default")
      (node (ref "MPU6000") (pin "8") (pinfunction "/CS_8") (pintype "input"))
      (node (ref "STM32F722") (pin "20") (pinfunction "PA4_20") (pintype "bidirectional"))
    )
    (net (code "69") (name "SPI1_SCLK") (class "Default")
      (node (ref "MPU6000") (pin "23") (pinfunction "SCL/SCLK_23") (pintype "input"))
      (node (ref "STM32F722") (pin "51") (pinfunction "PC10_51") (pintype "bidirectional"))
    )
    (net (code "70") (name "SPI2_MISO") (class "Default")
      (node (ref "NRF24L01") (pin "MISO") (pinfunction "MISO_MISO") (pintype "bidirectional"))
      (node (ref "STM32F722") (pin "10") (pinfunction "PC2_10") (pintype "bidirectional"))
    )
    (net (code "71") (name "SPI2_MOSI") (class "Default")
      (node (ref "NRF24L01") (pin "MOSI") (pinfunction "MOSI_MOSI") (pintype "bidirectional"))
      (node (ref "STM32F722") (pin "9") (pinfunction "PC1_9") (pintype "bidirectional"))
    )
    (net (code "72") (name "SPI2_NSS") (class "Default")
      (node (ref "NRF24L01") (pin "CSN") (pinfunction "CSN_CSN") (pintype "bidirectional"))
      (node (ref "STM32F722") (pin "33") (pinfunction "PB12_33") (pintype "bidirectional"))
    )
    (net (code "73") (name "SPI2_SCLK") (class "Default")
      (node (ref "NRF24L01") (pin "SCK") (pinfunction "SCK_SCK") (pintype "bidirectional"))
      (node (ref "STM32F722") (pin "34") (pinfunction "PB13_34") (pintype "bidirectional"))
    )
    (net (code "74") (name "SWCLK") (class "Default")
      (node (ref "JTAG") (pin "2") (pinfunction "2_2") (pintype "passive"))
      (node (ref "STM32F722") (pin "49") (pinfunction "PA14_49") (pintype "bidirectional"))
    )
    (net (code "75") (name "SWDIO") (class "Default")
      (node (ref "JTAG") (pin "4") (pinfunction "4_4") (pintype "passive"))
      (node (ref "STM32F722") (pin "46") (pinfunction "PA13_46") (pintype "bidirectional"))
    )
    (net (code "76") (name "SWO") (class "Default")
      (node (ref "JTAG") (pin "6") (pinfunction "6_6") (pintype "passive"))
      (node (ref "STM32F722") (pin "55") (pinfunction "PB3_55") (pintype "bidirectional"))
    )
    (net (code "77") (name "TRIGG1_IN") (class "Default")
      (node (ref "ATMEGA328P") (pin "30") (pinfunction "PD0(RXD)_30") (pintype "bidirectional"))
      (node (ref "SONIC1") (pin "2") (pinfunction "2_2") (pintype "bidirectional"))
    )
    (net (code "78") (name "TRIGG2_IN") (class "Default")
      (node (ref "ATMEGA328P") (pin "23") (pinfunction "PC0(ADC0)_23") (pintype "bidirectional"))
      (node (ref "SONIC2") (pin "2") (pinfunction "2_2") (pintype "bidirectional"))
    )
    (net (code "79") (name "TRIGG3_IN") (class "Default")
      (node (ref "ATMEGA328P") (pin "25") (pinfunction "PC2(ADC2)_25") (pintype "bidirectional"))
    )
    (net (code "80") (name "TRIGG4_IN") (class "Default")
      (node (ref "ATMEGA328P") (pin "1") (pinfunction "PD3(INT1)_1") (pintype "bidirectional"))
    )
    (net (code "81") (name "TRIGG5_IN") (class "Default")
      (node (ref "ATMEGA328P") (pin "9") (pinfunction "PD5(T1)_9") (pintype "bidirectional"))
    )
    (net (code "82") (name "TRIGG6_IN") (class "Default")
      (node (ref "ATMEGA328P") (pin "11") (pinfunction "PD7(AIN1)_11") (pintype "bidirectional"))
    )
    (net (code "83") (name "UART1_RX") (class "Default")
      (node (ref "FT232RL") (pin "1") (pinfunction "TXD_1") (pintype "output"))
      (node (ref "OSD") (pin "3") (pinfunction "3_3") (pintype "bidirectional"))
      (node (ref "STM32F722") (pin "43") (pinfunction "PA10_43") (pintype "bidirectional"))
    )
    (net (code "84") (name "UART1_TX") (class "Default")
      (node (ref "FT232RL") (pin "5") (pinfunction "RXD_5") (pintype "input"))
      (node (ref "OSD") (pin "4") (pinfunction "4_4") (pintype "bidirectional"))
      (node (ref "STM32F722") (pin "42") (pinfunction "PA9_42") (pintype "bidirectional"))
    )
    (net (code "85") (name "UART2_RX") (class "Default")
      (node (ref "GPS") (pin "3") (pinfunction "3_3") (pintype "bidirectional"))
      (node (ref "STM32F722") (pin "17") (pinfunction "PA3_17") (pintype "bidirectional"))
    )
    (net (code "86") (name "UART2_TX") (class "Default")
      (node (ref "GPS") (pin "4") (pinfunction "4_4") (pintype "bidirectional"))
      (node (ref "STM32F722") (pin "16") (pinfunction "PA2_16") (pintype "bidirectional"))
    )
    (net (code "87") (name "USBDM") (class "Default")
      (node (ref "FT232RL") (pin "16") (pinfunction "USBDM_16") (pintype "bidirectional"))
      (node (ref "USB") (pin "D-") (pinfunction "D-_D-") (pintype "bidirectional"))
    )
    (net (code "88") (name "USBDP") (class "Default")
      (node (ref "FT232RL") (pin "15") (pinfunction "USBDP_15") (pintype "bidirectional"))
      (node (ref "USB") (pin "D+") (pinfunction "D+_D+") (pintype "bidirectional"))
    )
    (net (code "89") (name "USBOSD") (class "Default")
      (node (ref "OSD/USB") (pin "2") (pinfunction "2_2") (pintype "passive"))
      (node (ref "STM32F722") (pin "45") (pinfunction "PA12_45") (pintype "bidirectional"))
    )
    (net (code "90") (name "VBAT") (class "Default")
      (node (ref "STM32F722") (pin "1") (pinfunction "VBAT_1") (pintype "power_in"))
    )
    (net (code "91") (name "VCC") (class "Default")
      (node (ref "BMP280") (pin "6") (pinfunction "VDDIO_6") (pintype "power_in"))
      (node (ref "BMP280") (pin "8") (pinfunction "VDD_8") (pintype "power_in"))
      (node (ref "C16") (pin "1") (pinfunction "1_1") (pintype "passive"))
      (node (ref "C17") (pin "1") (pinfunction "1_1") (pintype "passive"))
      (node (ref "C19") (pin "1") (pinfunction "1_1") (pintype "passive"))
      (node (ref "C2") (pin "1") (pinfunction "1_1") (pintype "passive"))
      (node (ref "C20") (pin "1") (pinfunction "1_1") (pintype "passive"))
      (node (ref "C22") (pin "1") (pinfunction "1_1") (pintype "passive"))
      (node (ref "C25") (pin "2") (pinfunction "2_2") (pintype "passive"))
      (node (ref "C27") (pin "1") (pinfunction "1_1") (pintype "passive"))
      (node (ref "C29") (pin "2") (pinfunction "2_2") (pintype "passive"))
      (node (ref "C3") (pin "1") (pinfunction "1_1") (pintype "passive"))
      (node (ref "C32") (pin "1") (pinfunction "1_1") (pintype "passive"))
      (node (ref "C33") (pin "1") (pinfunction "1_1") (pintype "passive"))
      (node (ref "C4") (pin "1") (pinfunction "1_1") (pintype "passive"))
      (node (ref "C5") (pin "1") (pinfunction "1_1") (pintype "passive"))
      (node (ref "C6") (pin "1") (pinfunction "1_1") (pintype "passive"))
      (node (ref "C7") (pin "1") (pinfunction "1_1") (pintype "passive"))
      (node (ref "DAC") (pin "2") (pinfunction "2_2") (pintype "passive"))
      (node (ref "FT232RL") (pin "4") (pinfunction "VCCIO_4") (pintype "power_in"))
      (node (ref "GIMBAL_X") (pin "2") (pinfunction "2_2") (pintype "passive"))
      (node (ref "GIMBAL_Y") (pin "2") (pinfunction "2_2") (pintype "passive"))
      (node (ref "GIMBAL_Z") (pin "2") (pinfunction "2_2") (pintype "passive"))
      (node (ref "GPS") (pin "1") (pinfunction "1_1") (pintype "bidirectional"))
      (node (ref "GY87") (pin "7") (pinfunction "7_7") (pintype "passive"))
      (node (ref "JTAG") (pin "1") (pinfunction "1_1") (pintype "passive"))
      (node (ref "LED6") (pin "A") (pinfunction "A_A") (pintype "passive"))
      (node (ref "LM3940-3.3") (pin "3") (pinfunction "OUT_3") (pintype "output"))
      (node (ref "MPU6000") (pin "13") (pinfunction "VDD_13") (pintype "power_in"))
      (node (ref "NRF24L01") (pin "VCC") (pinfunction "VCC_VCC") (pintype "power_in"))
      (node (ref "OSD") (pin "1") (pinfunction "1_1") (pintype "bidirectional"))
      (node (ref "OSD/USB") (pin "1") (pinfunction "1_1") (pintype "passive"))
      (node (ref "R2") (pin "2") (pinfunction "2_2") (pintype "passive"))
      (node (ref "R3") (pin "2") (pinfunction "2_2") (pintype "passive"))
      (node (ref "R4") (pin "2") (pinfunction "2_2") (pintype "passive"))
      (node (ref "R5") (pin "2") (pinfunction "2_2") (pintype "passive"))
      (node (ref "SD_CARD") (pin "4") (pinfunction "VDD_4") (pintype "power_in"))
      (node (ref "STM32F722") (pin "13") (pinfunction "VDDA_13") (pintype "power_in"))
      (node (ref "STM32F722") (pin "19") (pinfunction "VDD_2_19") (pintype "power_in"))
      (node (ref "STM32F722") (pin "32") (pinfunction "VDD_3_32") (pintype "power_in"))
      (node (ref "STM32F722") (pin "48") (pinfunction "VDD_4_48") (pintype "power_in"))
      (node (ref "STM32F722") (pin "64") (pinfunction "VDD_64") (pintype "power_in"))
      (node (ref "TXB0104") (pin "1") (pinfunction "VCCA_1") (pintype "bidirectional"))
    )
    (net (code "92") (name "VCC_2") (class "Default")
      (node (ref "ADC1") (pin "2") (pinfunction "2_2") (pintype "passive"))
      (node (ref "ADC2") (pin "2") (pinfunction "2_2") (pintype "passive"))
      (node (ref "ATMEGA328P") (pin "18") (pinfunction "AVCC_18") (pintype "bidirectional"))
      (node (ref "ATMEGA328P") (pin "4") (pinfunction "VCC_4") (pintype "bidirectional"))
      (node (ref "ATMEGA328P") (pin "6") (pinfunction "VCC_6") (pintype "bidirectional"))
      (node (ref "C13") (pin "1") (pinfunction "1_1") (pintype "passive"))
      (node (ref "C14") (pin "1") (pinfunction "1_1") (pintype "passive"))
      (node (ref "C15") (pin "1") (pinfunction "1_1") (pintype "passive"))
      (node (ref "C18") (pin "1") (pinfunction "1_1") (pintype "passive"))
      (node (ref "C21") (pin "1") (pinfunction "1_1") (pintype "passive"))
      (node (ref "C23") (pin "1") (pinfunction "1_1") (pintype "passive"))
      (node (ref "C28") (pin "2") (pinfunction "2_2") (pintype "passive"))
      (node (ref "C34") (pin "1") (pinfunction "1_1") (pintype "passive"))
      (node (ref "D1") (pin "C") (pinfunction "C_C") (pintype "passive"))
      (node (ref "FT232RL") (pin "20") (pinfunction "VCC_20") (pintype "power_in"))
      (node (ref "ICSP") (pin "2") (pinfunction "VCC_2") (pintype "power_in"))
      (node (ref "LED") (pin "1") (pinfunction "1_1") (pintype "passive"))
      (node (ref "LED1") (pin "A") (pinfunction "A_A") (pintype "passive"))
      (node (ref "LED2") (pin "A") (pinfunction "A_A") (pintype "passive"))
      (node (ref "LM3940-3.3") (pin "1") (pinfunction "IN_1") (pintype "power_in"))
      (node (ref "M1") (pin "2") (pinfunction "2_2") (pintype "passive"))
      (node (ref "M2") (pin "2") (pinfunction "2_2") (pintype "passive"))
      (node (ref "M3") (pin "2") (pinfunction "2_2") (pintype "passive"))
      (node (ref "M4") (pin "2") (pinfunction "2_2") (pintype "passive"))
      (node (ref "SONIC1") (pin "1") (pinfunction "1_1") (pintype "bidirectional"))
      (node (ref "SONIC2") (pin "1") (pinfunction "1_1") (pintype "bidirectional"))
      (node (ref "TXB0104") (pin "14") (pinfunction "VCCB_14") (pintype "bidirectional"))
    )
    (net (code "93") (name "V_USB") (class "Default")
      (node (ref "D1") (pin "A") (pinfunction "A_A") (pintype "passive"))
      (node (ref "USB") (pin "VBUS") (pinfunction "VBUS_VBUS") (pintype "power_in"))
    )
    (net (code "94") (name "unconnected-(FT232RL-3V3OUT-Pad17)") (class "Default")
      (node (ref "FT232RL") (pin "17") (pinfunction "3V3OUT_17") (pintype "output"))
    )
    (net (code "95") (name "unconnected-(FT232RL-CBUS2-Pad13)") (class "Default")
      (node (ref "FT232RL") (pin "13") (pinfunction "CBUS2_13") (pintype "bidirectional"))
    )
    (net (code "96") (name "unconnected-(FT232RL-CBUS3-Pad14)") (class "Default")
      (node (ref "FT232RL") (pin "14") (pinfunction "CBUS3_14") (pintype "bidirectional"))
    )
    (net (code "97") (name "unconnected-(FT232RL-CBUS4-Pad12)") (class "Default")
      (node (ref "FT232RL") (pin "12") (pinfunction "CBUS4_12") (pintype "bidirectional"))
    )
    (net (code "98") (name "unconnected-(FT232RL-OSCI-Pad27)") (class "Default")
      (node (ref "FT232RL") (pin "27") (pinfunction "OSCI_27") (pintype "input"))
    )
    (net (code "99") (name "unconnected-(FT232RL-OSCO-Pad28)") (class "Default")
      (node (ref "FT232RL") (pin "28") (pinfunction "OSCO_28") (pintype "output"))
    )
    (net (code "100") (name "unconnected-(FT232RL-~{CTS}-Pad11)") (class "Default")
      (node (ref "FT232RL") (pin "11") (pinfunction "~{CTS}_11") (pintype "input"))
    )
    (net (code "101") (name "unconnected-(FT232RL-~{DCD}-Pad10)") (class "Default")
      (node (ref "FT232RL") (pin "10") (pinfunction "~{DCD}_10") (pintype "input"))
    )
    (net (code "102") (name "unconnected-(FT232RL-~{DSR}-Pad9)") (class "Default")
      (node (ref "FT232RL") (pin "9") (pinfunction "~{DSR}_9") (pintype "input"))
    )
    (net (code "103") (name "unconnected-(FT232RL-~{DTR}-Pad2)") (class "Default")
      (node (ref "FT232RL") (pin "2") (pinfunction "~{DTR}_2") (pintype "output"))
    )
    (net (code "104") (name "unconnected-(FT232RL-~{RI}-Pad6)") (class "Default")
      (node (ref "FT232RL") (pin "6") (pinfunction "~{RI}_6") (pintype "input"))
    )
    (net (code "105") (name "unconnected-(FT232RL-~{RTS}-Pad3)") (class "Default")
      (node (ref "FT232RL") (pin "3") (pinfunction "~{RTS}_3") (pintype "output"))
    )
    (net (code "106") (name "unconnected-(GY87-Pad8)") (class "Default")
      (node (ref "GY87") (pin "8") (pinfunction "8_8") (pintype "passive"))
    )
    (net (code "107") (name "unconnected-(JP1-Pad1)") (class "Default")
      (node (ref "JP1") (pin "1") (pinfunction "1_1") (pintype "passive"))
    )
    (net (code "108") (name "unconnected-(JP1-Pad2)") (class "Default")
      (node (ref "JP1") (pin "2") (pinfunction "2_2") (pintype "passive"))
    )
    (net (code "109") (name "unconnected-(JP1-Pad3)") (class "Default")
      (node (ref "JP1") (pin "3") (pinfunction "3_3") (pintype "passive"))
    )
    (net (code "110") (name "unconnected-(JP1-Pad4)") (class "Default")
      (node (ref "JP1") (pin "4") (pinfunction "4_4") (pintype "passive"))
    )
    (net (code "111") (name "unconnected-(JP1-Pad5)") (class "Default")
      (node (ref "JP1") (pin "5") (pinfunction "5_5") (pintype "passive"))
    )
    (net (code "112") (name "unconnected-(JP1-Pad6)") (class "Default")
      (node (ref "JP1") (pin "6") (pinfunction "6_6") (pintype "passive"))
    )
    (net (code "113") (name "unconnected-(JP2-Pad1)") (class "Default")
      (node (ref "JP2") (pin "1") (pinfunction "1_1") (pintype "passive"))
    )
    (net (code "114") (name "unconnected-(JP2-Pad2)") (class "Default")
      (node (ref "JP2") (pin "2") (pinfunction "2_2") (pintype "passive"))
    )
    (net (code "115") (name "unconnected-(JP2-Pad3)") (class "Default")
      (node (ref "JP2") (pin "3") (pinfunction "3_3") (pintype "passive"))
    )
    (net (code "116") (name "unconnected-(JP2-Pad4)") (class "Default")
      (node (ref "JP2") (pin "4") (pinfunction "4_4") (pintype "passive"))
    )
    (net (code "117") (name "unconnected-(JP2-Pad5)") (class "Default")
      (node (ref "JP2") (pin "5") (pinfunction "5_5") (pintype "passive"))
    )
    (net (code "118") (name "unconnected-(JP2-Pad6)") (class "Default")
      (node (ref "JP2") (pin "6") (pinfunction "6_6") (pintype "passive"))
    )
    (net (code "119") (name "unconnected-(JP3-Pad1)") (class "Default")
      (node (ref "JP3") (pin "1") (pinfunction "1_1") (pintype "passive"))
    )
    (net (code "120") (name "unconnected-(JP3-Pad2)") (class "Default")
      (node (ref "JP3") (pin "2") (pinfunction "2_2") (pintype "passive"))
    )
    (net (code "121") (name "unconnected-(JP3-Pad3)") (class "Default")
      (node (ref "JP3") (pin "3") (pinfunction "3_3") (pintype "passive"))
    )
    (net (code "122") (name "unconnected-(JP3-Pad4)") (class "Default")
      (node (ref "JP3") (pin "4") (pinfunction "4_4") (pintype "passive"))
    )
    (net (code "123") (name "unconnected-(JP3-Pad5)") (class "Default")
      (node (ref "JP3") (pin "5") (pinfunction "5_5") (pintype "passive"))
    )
    (net (code "124") (name "unconnected-(JP3-Pad6)") (class "Default")
      (node (ref "JP3") (pin "6") (pinfunction "6_6") (pintype "passive"))
    )
    (net (code "125") (name "unconnected-(JP4-Pad1)") (class "Default")
      (node (ref "JP4") (pin "1") (pinfunction "1_1") (pintype "passive"))
    )
    (net (code "126") (name "unconnected-(JP4-Pad2)") (class "Default")
      (node (ref "JP4") (pin "2") (pinfunction "2_2") (pintype "passive"))
    )
    (net (code "127") (name "unconnected-(JP4-Pad3)") (class "Default")
      (node (ref "JP4") (pin "3") (pinfunction "3_3") (pintype "passive"))
    )
    (net (code "128") (name "unconnected-(JP4-Pad4)") (class "Default")
      (node (ref "JP4") (pin "4") (pinfunction "4_4") (pintype "passive"))
    )
    (net (code "129") (name "unconnected-(JP4-Pad5)") (class "Default")
      (node (ref "JP4") (pin "5") (pinfunction "5_5") (pintype "passive"))
    )
    (net (code "130") (name "unconnected-(JP4-Pad6)") (class "Default")
      (node (ref "JP4") (pin "6") (pinfunction "6_6") (pintype "passive"))
    )
    (net (code "131") (name "unconnected-(JP5-Pad1)") (class "Default")
      (node (ref "JP5") (pin "1") (pinfunction "1_1") (pintype "passive"))
    )
    (net (code "132") (name "unconnected-(JP5-Pad2)") (class "Default")
      (node (ref "JP5") (pin "2") (pinfunction "2_2") (pintype "passive"))
    )
    (net (code "133") (name "unconnected-(JP5-Pad3)") (class "Default")
      (node (ref "JP5") (pin "3") (pinfunction "3_3") (pintype "passive"))
    )
    (net (code "134") (name "unconnected-(JP5-Pad4)") (class "Default")
      (node (ref "JP5") (pin "4") (pinfunction "4_4") (pintype "passive"))
    )
    (net (code "135") (name "unconnected-(JP5-Pad5)") (class "Default")
      (node (ref "JP5") (pin "5") (pinfunction "5_5") (pintype "passive"))
    )
    (net (code "136") (name "unconnected-(JP5-Pad6)") (class "Default")
      (node (ref "JP5") (pin "6") (pinfunction "6_6") (pintype "passive"))
    )
    (net (code "137") (name "unconnected-(JP6-Pad1)") (class "Default")
      (node (ref "JP6") (pin "1") (pinfunction "1_1") (pintype "passive"))
    )
    (net (code "138") (name "unconnected-(JP6-Pad2)") (class "Default")
      (node (ref "JP6") (pin "2") (pinfunction "2_2") (pintype "passive"))
    )
    (net (code "139") (name "unconnected-(JP6-Pad3)") (class "Default")
      (node (ref "JP6") (pin "3") (pinfunction "3_3") (pintype "passive"))
    )
    (net (code "140") (name "unconnected-(JP6-Pad4)") (class "Default")
      (node (ref "JP6") (pin "4") (pinfunction "4_4") (pintype "passive"))
    )
    (net (code "141") (name "unconnected-(JP6-Pad5)") (class "Default")
      (node (ref "JP6") (pin "5") (pinfunction "5_5") (pintype "passive"))
    )
    (net (code "142") (name "unconnected-(JP6-Pad6)") (class "Default")
      (node (ref "JP6") (pin "6") (pinfunction "6_6") (pintype "passive"))
    )
    (net (code "143") (name "unconnected-(JP7-Pad1)") (class "Default")
      (node (ref "JP7") (pin "1") (pinfunction "1_1") (pintype "passive"))
    )
    (net (code "144") (name "unconnected-(JP7-Pad2)") (class "Default")
      (node (ref "JP7") (pin "2") (pinfunction "2_2") (pintype "passive"))
    )
    (net (code "145") (name "unconnected-(JP7-Pad3)") (class "Default")
      (node (ref "JP7") (pin "3") (pinfunction "3_3") (pintype "passive"))
    )
    (net (code "146") (name "unconnected-(JP7-Pad4)") (class "Default")
      (node (ref "JP7") (pin "4") (pinfunction "4_4") (pintype "passive"))
    )
    (net (code "147") (name "unconnected-(JP7-Pad5)") (class "Default")
      (node (ref "JP7") (pin "5") (pinfunction "5_5") (pintype "passive"))
    )
    (net (code "148") (name "unconnected-(JP7-Pad6)") (class "Default")
      (node (ref "JP7") (pin "6") (pinfunction "6_6") (pintype "passive"))
    )
    (net (code "149") (name "unconnected-(MPU6000A-AUX_CL-Pad7)") (class "Default")
      (node (ref "MPU6000") (pin "7") (pinfunction "AUX_CL_7") (pintype "bidirectional"))
    )
    (net (code "150") (name "unconnected-(MPU6000A-AUX_DA-Pad6)") (class "Default")
      (node (ref "MPU6000") (pin "6") (pinfunction "AUX_DA_6") (pintype "bidirectional"))
    )
    (net (code "151") (name "unconnected-(MPU6000A-RESV-Pad19)") (class "Default")
      (node (ref "MPU6000") (pin "19") (pinfunction "RESV_19") (pintype "passive"))
    )
    (net (code "152") (name "unconnected-(MPU6000A-RESV-Pad21)") (class "Default")
      (node (ref "MPU6000") (pin "21") (pinfunction "RESV_21") (pintype "passive"))
    )
    (net (code "153") (name "unconnected-(MPU6000A-RESV-Pad22)") (class "Default")
      (node (ref "MPU6000") (pin "22") (pinfunction "RESV_22") (pintype "passive"))
    )
    (net (code "154") (name "unconnected-(SD_CARD-DAT1-Pad8)") (class "Default")
      (node (ref "SD_CARD") (pin "8") (pinfunction "DAT1_8") (pintype "bidirectional"))
    )
    (net (code "155") (name "unconnected-(SD_CARD-DAT2-Pad1)") (class "Default")
      (node (ref "SD_CARD") (pin "1") (pinfunction "DAT2_1") (pintype "bidirectional"))
    )
    (net (code "156") (name "unconnected-(SD_CARD-DAT3{slash}CD-Pad2)") (class "Default")
      (node (ref "SD_CARD") (pin "2") (pinfunction "DAT3/CD_2") (pintype "bidirectional"))
    )
    (net (code "157") (name "unconnected-(STM32F722A-PA15-Pad50)") (class "Default")
      (node (ref "STM32F722") (pin "50") (pinfunction "PA15_50") (pintype "bidirectional"))
    )
    (net (code "158") (name "unconnected-(STM32F722A-PB14-Pad35)") (class "Default")
      (node (ref "STM32F722") (pin "35") (pinfunction "PB14_35") (pintype "bidirectional"))
    )
    (net (code "159") (name "unconnected-(STM32F722A-PB15-Pad36)") (class "Default")
      (node (ref "STM32F722") (pin "36") (pinfunction "PB15_36") (pintype "bidirectional"))
    )
    (net (code "160") (name "unconnected-(STM32F722A-PC0-Pad8)") (class "Default")
      (node (ref "STM32F722") (pin "8") (pinfunction "PC0_8") (pintype "bidirectional"))
    )
    (net (code "161") (name "unconnected-(STM32F722A-PC3-Pad11)") (class "Default")
      (node (ref "STM32F722") (pin "11") (pinfunction "PC3_11") (pintype "bidirectional"))
    )
    (net (code "162") (name "unconnected-(STM32F722A-PC13-Pad2)") (class "Default")
      (node (ref "STM32F722") (pin "2") (pinfunction "PC13_2") (pintype "bidirectional"))
    )
    (net (code "163") (name "unconnected-(STM32F722A-PC14-OSC32_IN-Pad3)") (class "Default")
      (node (ref "STM32F722") (pin "3") (pinfunction "PC14-OSC32_IN_3") (pintype "bidirectional"))
    )
    (net (code "164") (name "unconnected-(STM32F722A-PC15-OSC32_OUT-Pad4)") (class "Default")
      (node (ref "STM32F722") (pin "4") (pinfunction "PC15-OSC32_OUT_4") (pintype "bidirectional"))
    )
    (net (code "165") (name "unconnected-(USB-PadID)") (class "Default")
      (node (ref "USB") (pin "ID") (pinfunction "ID_ID") (pintype "bidirectional"))
    )
  )
)
